# teensyShield1_10.net
KiCad netlist of a schematic drawn in EAGLE
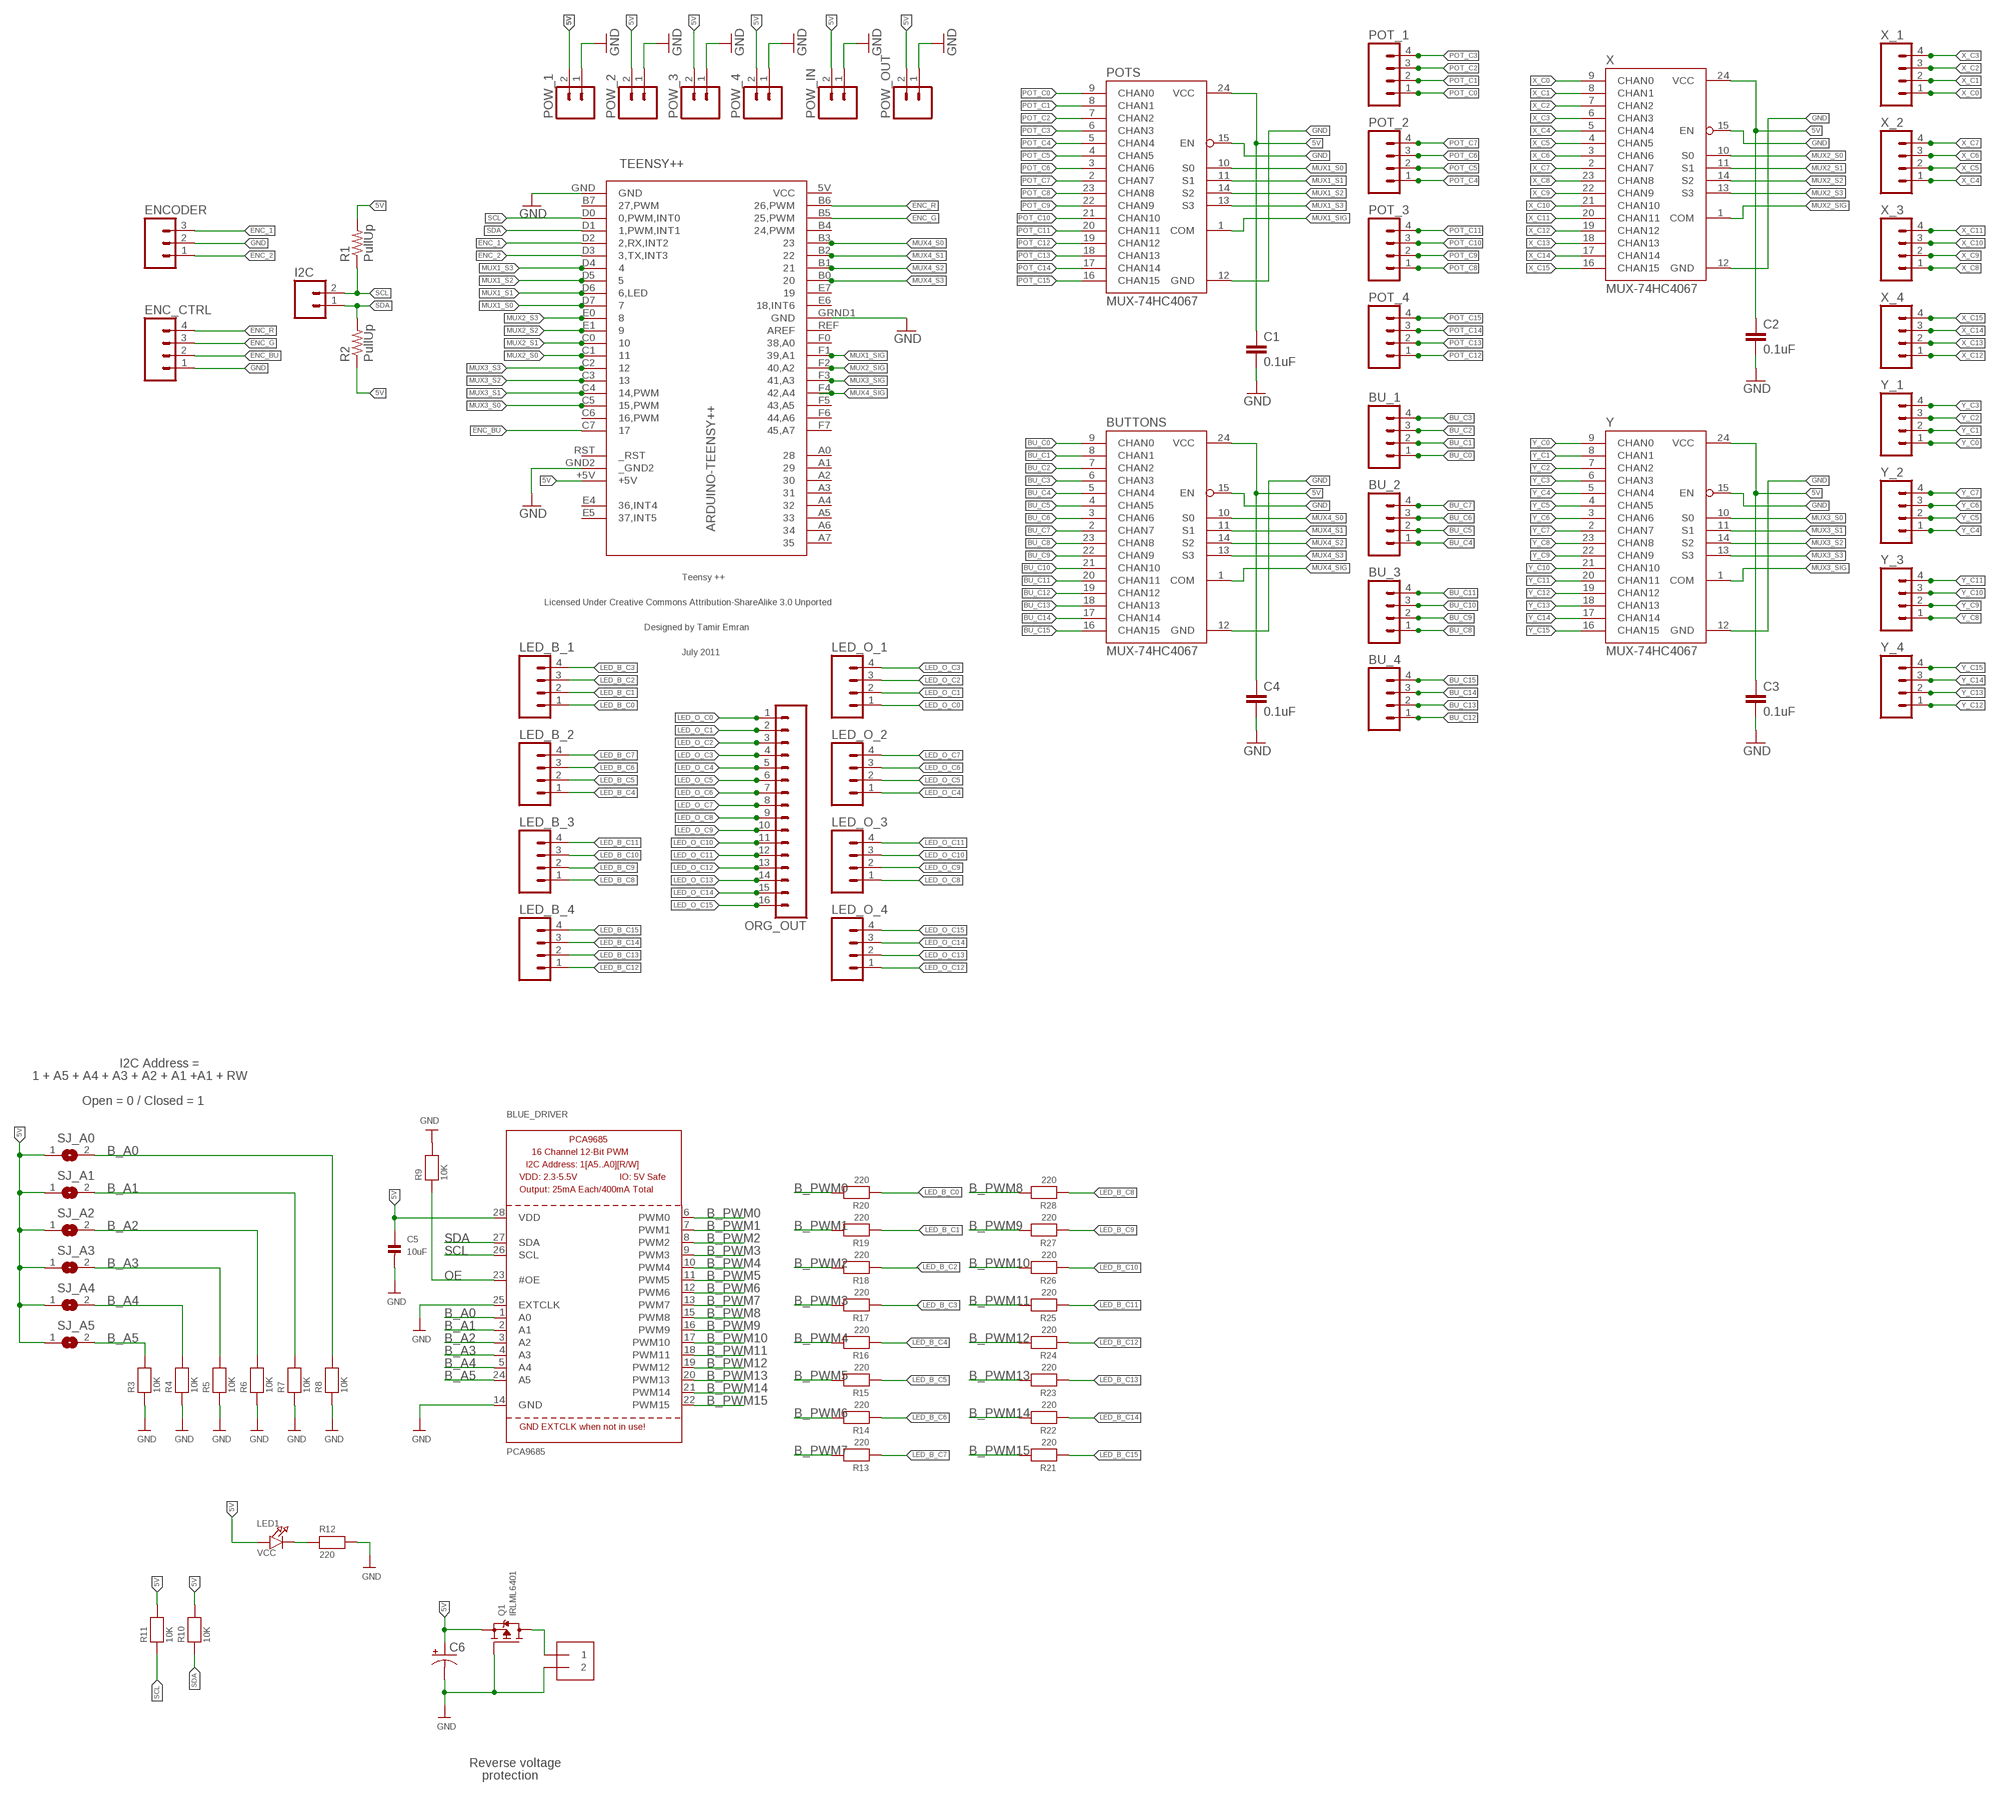
[diagram p0: schematic, sheet 1]

(export (version "E")
  (design (tool "Eeschema 10.0.6"))
  (components
    (comp (ref "BLUE_DRIVER")
      (value "PCA9685")
      (footprint "eagle-import:TSSOP28")
      (libsource (lib "eagle-import") (part "PCA9685"))
    )
    (comp (ref "BUTTONS")
      (value "MUX-74HC4067")
      (footprint "eagle-import:SSOP24")
      (libsource (lib "eagle-import") (part "MUX-74HC4067SMD"))
    )
    (comp (ref "BU_1")
      (value "M04NO_SILK_ALL_ROUND")
      (footprint "eagle-import:1X04_NO_SILK_ALL_ROUND")
      (libsource (lib "eagle-import") (part "M04NO_SILK_ALL_ROUND"))
    )
    (comp (ref "BU_2")
      (value "M04NO_SILK_ALL_ROUND")
      (footprint "eagle-import:1X04_NO_SILK_ALL_ROUND")
      (libsource (lib "eagle-import") (part "M04NO_SILK_ALL_ROUND"))
    )
    (comp (ref "BU_3")
      (value "M04NO_SILK_ALL_ROUND")
      (footprint "eagle-import:1X04_NO_SILK_ALL_ROUND")
      (libsource (lib "eagle-import") (part "M04NO_SILK_ALL_ROUND"))
    )
    (comp (ref "BU_4")
      (value "M04NO_SILK_ALL_ROUND")
      (footprint "eagle-import:1X04_NO_SILK_ALL_ROUND")
      (libsource (lib "eagle-import") (part "M04NO_SILK_ALL_ROUND"))
    )
    (comp (ref "C1")
      (value "0.1uF")
      (footprint "eagle-import:0603")
      (libsource (lib "eagle-import") (part "CAP0603"))
    )
    (comp (ref "C2")
      (value "0.1uF")
      (footprint "eagle-import:0603")
      (libsource (lib "eagle-import") (part "CAP0603"))
    )
    (comp (ref "C3")
      (value "0.1uF")
      (footprint "eagle-import:0603")
      (libsource (lib "eagle-import") (part "CAP0603"))
    )
    (comp (ref "C4")
      (value "0.1uF")
      (footprint "eagle-import:0603")
      (libsource (lib "eagle-import") (part "CAP0603"))
    )
    (comp (ref "C5")
      (value "10uF")
      (footprint "eagle-import:0805")
      (libsource (lib "eagle-import") (part "CAP_CERAMIC0805"))
    )
    (comp (ref "C6")
      (value "CPOL-USE3.5-8")
      (footprint "eagle-import:E3,5-8")
      (libsource (lib "eagle-import") (part "CPOL-USE3.5-8"))
    )
    (comp (ref "ENCODER")
      (value "M031X03_NO_SILK")
      (footprint "eagle-import:1X03_NO_SILK")
      (libsource (lib "eagle-import") (part "M031X03_NO_SILK"))
    )
    (comp (ref "ENC_CTRL")
      (value "M041X04_NO_SILK")
      (footprint "eagle-import:1X04_NO_SILK")
      (libsource (lib "eagle-import") (part "M041X04_NO_SILK"))
    )
    (comp (ref "I2C")
      (value "M02LOCK")
      (footprint "eagle-import:1X02_LOCK")
      (libsource (lib "eagle-import") (part "M02LOCK"))
    )
    (comp (ref "J1")
      (value "TERMBLOCK_1X2-3.5MM")
      (footprint "eagle-import:1X2-3.5MM")
      (libsource (lib "eagle-import") (part "TERMBLOCK_1X2-3.5MM"))
    )
    (comp (ref "LED1")
      (value "VCC")
      (footprint "eagle-import:CHIPLED_0805")
      (libsource (lib "eagle-import") (part "LED0805"))
    )
    (comp (ref "LED_B_1")
      (value "M04NO_SILK_ALL_ROUND")
      (footprint "eagle-import:1X04_NO_SILK_ALL_ROUND")
      (libsource (lib "eagle-import") (part "M04NO_SILK_ALL_ROUND"))
    )
    (comp (ref "LED_B_2")
      (value "M04NO_SILK_ALL_ROUND")
      (footprint "eagle-import:1X04_NO_SILK_ALL_ROUND")
      (libsource (lib "eagle-import") (part "M04NO_SILK_ALL_ROUND"))
    )
    (comp (ref "LED_B_3")
      (value "M04NO_SILK_ALL_ROUND")
      (footprint "eagle-import:1X04_NO_SILK_ALL_ROUND")
      (libsource (lib "eagle-import") (part "M04NO_SILK_ALL_ROUND"))
    )
    (comp (ref "LED_B_4")
      (value "M04NO_SILK_ALL_ROUND")
      (footprint "eagle-import:1X04_NO_SILK_ALL_ROUND")
      (libsource (lib "eagle-import") (part "M04NO_SILK_ALL_ROUND"))
    )
    (comp (ref "LED_O_1")
      (value "M04NO_SILK_ALL_ROUND")
      (footprint "eagle-import:1X04_NO_SILK_ALL_ROUND")
      (libsource (lib "eagle-import") (part "M04NO_SILK_ALL_ROUND"))
    )
    (comp (ref "LED_O_2")
      (value "M04NO_SILK_ALL_ROUND")
      (footprint "eagle-import:1X04_NO_SILK_ALL_ROUND")
      (libsource (lib "eagle-import") (part "M04NO_SILK_ALL_ROUND"))
    )
    (comp (ref "LED_O_3")
      (value "M04NO_SILK_ALL_ROUND")
      (footprint "eagle-import:1X04_NO_SILK_ALL_ROUND")
      (libsource (lib "eagle-import") (part "M04NO_SILK_ALL_ROUND"))
    )
    (comp (ref "LED_O_4")
      (value "M04NO_SILK_ALL_ROUND")
      (footprint "eagle-import:1X04_NO_SILK_ALL_ROUND")
      (libsource (lib "eagle-import") (part "M04NO_SILK_ALL_ROUND"))
    )
    (comp (ref "ORG_OUT")
      (value "M161X16_NO_SILK")
      (footprint "eagle-import:1X16_NO_SILK")
      (libsource (lib "eagle-import") (part "M161X16_NO_SILK"))
    )
    (comp (ref "POTS")
      (value "MUX-74HC4067")
      (footprint "eagle-import:SSOP24")
      (libsource (lib "eagle-import") (part "MUX-74HC4067SMD"))
    )
    (comp (ref "POT_1")
      (value "M04NO_SILK_ALL_ROUND")
      (footprint "eagle-import:1X04_NO_SILK_ALL_ROUND")
      (libsource (lib "eagle-import") (part "M04NO_SILK_ALL_ROUND"))
    )
    (comp (ref "POT_2")
      (value "M04NO_SILK_ALL_ROUND")
      (footprint "eagle-import:1X04_NO_SILK_ALL_ROUND")
      (libsource (lib "eagle-import") (part "M04NO_SILK_ALL_ROUND"))
    )
    (comp (ref "POT_3")
      (value "M04NO_SILK_ALL_ROUND")
      (footprint "eagle-import:1X04_NO_SILK_ALL_ROUND")
      (libsource (lib "eagle-import") (part "M04NO_SILK_ALL_ROUND"))
    )
    (comp (ref "POT_4")
      (value "M04NO_SILK_ALL_ROUND")
      (footprint "eagle-import:1X04_NO_SILK_ALL_ROUND")
      (libsource (lib "eagle-import") (part "M04NO_SILK_ALL_ROUND"))
    )
    (comp (ref "POW_1")
      (value "M02POLAR")
      (footprint "eagle-import:MOLEX-1X2")
      (libsource (lib "eagle-import") (part "M02POLAR"))
    )
    (comp (ref "POW_2")
      (value "M02POLAR")
      (footprint "eagle-import:MOLEX-1X2")
      (libsource (lib "eagle-import") (part "M02POLAR"))
    )
    (comp (ref "POW_3")
      (value "M02POLAR")
      (footprint "eagle-import:MOLEX-1X2")
      (libsource (lib "eagle-import") (part "M02POLAR"))
    )
    (comp (ref "POW_4")
      (value "M02POLAR")
      (footprint "eagle-import:MOLEX-1X2")
      (libsource (lib "eagle-import") (part "M02POLAR"))
    )
    (comp (ref "POW_IN")
      (value "M02POLAR")
      (footprint "eagle-import:MOLEX-1X2")
      (libsource (lib "eagle-import") (part "M02POLAR"))
    )
    (comp (ref "POW_OUT")
      (value "M02POLAR")
      (footprint "eagle-import:MOLEX-1X2")
      (libsource (lib "eagle-import") (part "M02POLAR"))
    )
    (comp (ref "Q1")
      (value "IRLML6401")
      (footprint "eagle-import:SOT23-WIDE")
      (libsource (lib "eagle-import") (part "MOSFET-PWIDE"))
    )
    (comp (ref "R1")
      (value "PullUp")
      (footprint "eagle-import:AXIAL-0.3")
      (libsource (lib "eagle-import") (part "10KOHM-1/4W5%(PTH)"))
    )
    (comp (ref "R2")
      (value "PullUp")
      (footprint "eagle-import:AXIAL-0.3")
      (libsource (lib "eagle-import") (part "10KOHM-1/4W5%(PTH)"))
    )
    (comp (ref "R3")
      (value "10K")
      (footprint "eagle-import:0805")
      (libsource (lib "eagle-import") (part "RESISTOR0805"))
    )
    (comp (ref "R4")
      (value "10K")
      (footprint "eagle-import:0805")
      (libsource (lib "eagle-import") (part "RESISTOR0805"))
    )
    (comp (ref "R5")
      (value "10K")
      (footprint "eagle-import:0805")
      (libsource (lib "eagle-import") (part "RESISTOR0805"))
    )
    (comp (ref "R6")
      (value "10K")
      (footprint "eagle-import:0805")
      (libsource (lib "eagle-import") (part "RESISTOR0805"))
    )
    (comp (ref "R7")
      (value "10K")
      (footprint "eagle-import:0805")
      (libsource (lib "eagle-import") (part "RESISTOR0805"))
    )
    (comp (ref "R8")
      (value "10K")
      (footprint "eagle-import:0805")
      (libsource (lib "eagle-import") (part "RESISTOR0805"))
    )
    (comp (ref "R9")
      (value "10K")
      (footprint "eagle-import:0805")
      (libsource (lib "eagle-import") (part "RESISTOR0805"))
    )
    (comp (ref "R10")
      (value "10K")
      (footprint "eagle-import:0805")
      (libsource (lib "eagle-import") (part "RESISTOR0805"))
    )
    (comp (ref "R11")
      (value "10K")
      (footprint "eagle-import:0805")
      (libsource (lib "eagle-import") (part "RESISTOR0805"))
    )
    (comp (ref "R12")
      (value "220")
      (footprint "eagle-import:0805")
      (libsource (lib "eagle-import") (part "RESISTOR0805"))
    )
    (comp (ref "R13")
      (value "220")
      (footprint "eagle-import:0805")
      (libsource (lib "eagle-import") (part "RESISTOR0805"))
    )
    (comp (ref "R14")
      (value "220")
      (footprint "eagle-import:0805")
      (libsource (lib "eagle-import") (part "RESISTOR0805"))
    )
    (comp (ref "R15")
      (value "220")
      (footprint "eagle-import:0805")
      (libsource (lib "eagle-import") (part "RESISTOR0805"))
    )
    (comp (ref "R16")
      (value "220")
      (footprint "eagle-import:0805")
      (libsource (lib "eagle-import") (part "RESISTOR0805"))
    )
    (comp (ref "R17")
      (value "220")
      (footprint "eagle-import:0805")
      (libsource (lib "eagle-import") (part "RESISTOR0805"))
    )
    (comp (ref "R18")
      (value "220")
      (footprint "eagle-import:0805")
      (libsource (lib "eagle-import") (part "RESISTOR0805"))
    )
    (comp (ref "R19")
      (value "220")
      (footprint "eagle-import:0805")
      (libsource (lib "eagle-import") (part "RESISTOR0805"))
    )
    (comp (ref "R20")
      (value "220")
      (footprint "eagle-import:0805")
      (libsource (lib "eagle-import") (part "RESISTOR0805"))
    )
    (comp (ref "R21")
      (value "220")
      (footprint "eagle-import:0805")
      (libsource (lib "eagle-import") (part "RESISTOR0805"))
    )
    (comp (ref "R22")
      (value "220")
      (footprint "eagle-import:0805")
      (libsource (lib "eagle-import") (part "RESISTOR0805"))
    )
    (comp (ref "R23")
      (value "220")
      (footprint "eagle-import:0805")
      (libsource (lib "eagle-import") (part "RESISTOR0805"))
    )
    (comp (ref "R24")
      (value "220")
      (footprint "eagle-import:0805")
      (libsource (lib "eagle-import") (part "RESISTOR0805"))
    )
    (comp (ref "R25")
      (value "220")
      (footprint "eagle-import:0805")
      (libsource (lib "eagle-import") (part "RESISTOR0805"))
    )
    (comp (ref "R26")
      (value "220")
      (footprint "eagle-import:0805")
      (libsource (lib "eagle-import") (part "RESISTOR0805"))
    )
    (comp (ref "R27")
      (value "220")
      (footprint "eagle-import:0805")
      (libsource (lib "eagle-import") (part "RESISTOR0805"))
    )
    (comp (ref "R28")
      (value "220")
      (footprint "eagle-import:0805")
      (libsource (lib "eagle-import") (part "RESISTOR0805"))
    )
    (comp (ref "SJ_A0")
      (value "SOLDERJUMPERREFLOW_NOPASTE")
      (footprint "eagle-import:SOLDERJUMPER_REFLOW_NOPASTE")
      (libsource (lib "eagle-import") (part "SOLDERJUMPERREFLOW_NOPASTE"))
    )
    (comp (ref "SJ_A1")
      (value "SOLDERJUMPERREFLOW_NOPASTE")
      (footprint "eagle-import:SOLDERJUMPER_REFLOW_NOPASTE")
      (libsource (lib "eagle-import") (part "SOLDERJUMPERREFLOW_NOPASTE"))
    )
    (comp (ref "SJ_A2")
      (value "SOLDERJUMPERREFLOW_NOPASTE")
      (footprint "eagle-import:SOLDERJUMPER_REFLOW_NOPASTE")
      (libsource (lib "eagle-import") (part "SOLDERJUMPERREFLOW_NOPASTE"))
    )
    (comp (ref "SJ_A3")
      (value "SOLDERJUMPERREFLOW_NOPASTE")
      (footprint "eagle-import:SOLDERJUMPER_REFLOW_NOPASTE")
      (libsource (lib "eagle-import") (part "SOLDERJUMPERREFLOW_NOPASTE"))
    )
    (comp (ref "SJ_A4")
      (value "SOLDERJUMPERREFLOW_NOPASTE")
      (footprint "eagle-import:SOLDERJUMPER_REFLOW_NOPASTE")
      (libsource (lib "eagle-import") (part "SOLDERJUMPERREFLOW_NOPASTE"))
    )
    (comp (ref "SJ_A5")
      (value "SOLDERJUMPERREFLOW_NOPASTE")
      (footprint "eagle-import:SOLDERJUMPER_REFLOW_NOPASTE")
      (libsource (lib "eagle-import") (part "SOLDERJUMPERREFLOW_NOPASTE"))
    )
    (comp (ref "TEENSY++")
      (value "ARDUINO-TEENSY++")
      (footprint "eagle-import:TEENSY++")
      (libsource (lib "eagle-import") (part "ARDUINO-TEENSY++"))
    )
    (comp (ref "X")
      (value "MUX-74HC4067")
      (footprint "eagle-import:SSOP24")
      (libsource (lib "eagle-import") (part "MUX-74HC4067SMD"))
    )
    (comp (ref "X_1")
      (value "M04NO_SILK_ALL_ROUND")
      (footprint "eagle-import:1X04_NO_SILK_ALL_ROUND")
      (libsource (lib "eagle-import") (part "M04NO_SILK_ALL_ROUND"))
    )
    (comp (ref "X_2")
      (value "M04NO_SILK_ALL_ROUND")
      (footprint "eagle-import:1X04_NO_SILK_ALL_ROUND")
      (libsource (lib "eagle-import") (part "M04NO_SILK_ALL_ROUND"))
    )
    (comp (ref "X_3")
      (value "M04NO_SILK_ALL_ROUND")
      (footprint "eagle-import:1X04_NO_SILK_ALL_ROUND")
      (libsource (lib "eagle-import") (part "M04NO_SILK_ALL_ROUND"))
    )
    (comp (ref "X_4")
      (value "M04NO_SILK_ALL_ROUND")
      (footprint "eagle-import:1X04_NO_SILK_ALL_ROUND")
      (libsource (lib "eagle-import") (part "M04NO_SILK_ALL_ROUND"))
    )
    (comp (ref "Y")
      (value "MUX-74HC4067")
      (footprint "eagle-import:SSOP24")
      (libsource (lib "eagle-import") (part "MUX-74HC4067SMD"))
    )
    (comp (ref "Y_1")
      (value "M04NO_SILK_ALL_ROUND")
      (footprint "eagle-import:1X04_NO_SILK_ALL_ROUND")
      (libsource (lib "eagle-import") (part "M04NO_SILK_ALL_ROUND"))
    )
    (comp (ref "Y_2")
      (value "M04NO_SILK_ALL_ROUND")
      (footprint "eagle-import:1X04_NO_SILK_ALL_ROUND")
      (libsource (lib "eagle-import") (part "M04NO_SILK_ALL_ROUND"))
    )
    (comp (ref "Y_3")
      (value "M04NO_SILK_ALL_ROUND")
      (footprint "eagle-import:1X04_NO_SILK_ALL_ROUND")
      (libsource (lib "eagle-import") (part "M04NO_SILK_ALL_ROUND"))
    )
    (comp (ref "Y_4")
      (value "M04NO_SILK_ALL_ROUND")
      (footprint "eagle-import:1X04_NO_SILK_ALL_ROUND")
      (libsource (lib "eagle-import") (part "M04NO_SILK_ALL_ROUND"))
    )
  )
  (nets
    (net (code "1") (name "/B_A0") (class "Default")
      (node (ref "BLUE_DRIVER") (pin "1") (pinfunction "A0_1") (pintype "bidirectional"))
      (node (ref "R8") (pin "2") (pinfunction "2_2") (pintype "passive"))
      (node (ref "SJ_A0") (pin "2") (pinfunction "2_2") (pintype "passive"))
    )
    (net (code "2") (name "/B_A1") (class "Default")
      (node (ref "BLUE_DRIVER") (pin "2") (pinfunction "A1_2") (pintype "bidirectional"))
      (node (ref "R7") (pin "2") (pinfunction "2_2") (pintype "passive"))
      (node (ref "SJ_A1") (pin "2") (pinfunction "2_2") (pintype "passive"))
    )
    (net (code "3") (name "/B_A2") (class "Default")
      (node (ref "BLUE_DRIVER") (pin "3") (pinfunction "A2_3") (pintype "bidirectional"))
      (node (ref "R6") (pin "2") (pinfunction "2_2") (pintype "passive"))
      (node (ref "SJ_A2") (pin "2") (pinfunction "2_2") (pintype "passive"))
    )
    (net (code "4") (name "/B_A3") (class "Default")
      (node (ref "BLUE_DRIVER") (pin "4") (pinfunction "A3_4") (pintype "bidirectional"))
      (node (ref "R5") (pin "2") (pinfunction "2_2") (pintype "passive"))
      (node (ref "SJ_A3") (pin "2") (pinfunction "2_2") (pintype "passive"))
    )
    (net (code "5") (name "/B_A4") (class "Default")
      (node (ref "BLUE_DRIVER") (pin "5") (pinfunction "A4_5") (pintype "bidirectional"))
      (node (ref "R4") (pin "2") (pinfunction "2_2") (pintype "passive"))
      (node (ref "SJ_A4") (pin "2") (pinfunction "2_2") (pintype "passive"))
    )
    (net (code "6") (name "/B_A5") (class "Default")
      (node (ref "BLUE_DRIVER") (pin "24") (pinfunction "A5_24") (pintype "bidirectional"))
      (node (ref "R3") (pin "2") (pinfunction "2_2") (pintype "passive"))
      (node (ref "SJ_A5") (pin "2") (pinfunction "2_2") (pintype "passive"))
    )
    (net (code "7") (name "/B_PWM0") (class "Default")
      (node (ref "BLUE_DRIVER") (pin "6") (pinfunction "PWM0_6") (pintype "output"))
      (node (ref "R20") (pin "2") (pinfunction "2_2") (pintype "passive"))
    )
    (net (code "8") (name "/B_PWM1") (class "Default")
      (node (ref "BLUE_DRIVER") (pin "7") (pinfunction "PWM1_7") (pintype "output"))
      (node (ref "R19") (pin "2") (pinfunction "2_2") (pintype "passive"))
    )
    (net (code "9") (name "/B_PWM2") (class "Default")
      (node (ref "BLUE_DRIVER") (pin "8") (pinfunction "PWM2_8") (pintype "output"))
      (node (ref "R18") (pin "2") (pinfunction "2_2") (pintype "passive"))
    )
    (net (code "10") (name "/B_PWM3") (class "Default")
      (node (ref "BLUE_DRIVER") (pin "9") (pinfunction "PWM3_9") (pintype "output"))
      (node (ref "R17") (pin "2") (pinfunction "2_2") (pintype "passive"))
    )
    (net (code "11") (name "/B_PWM4") (class "Default")
      (node (ref "BLUE_DRIVER") (pin "10") (pinfunction "PWM4_10") (pintype "output"))
      (node (ref "R16") (pin "2") (pinfunction "2_2") (pintype "passive"))
    )
    (net (code "12") (name "/B_PWM5") (class "Default")
      (node (ref "BLUE_DRIVER") (pin "11") (pinfunction "PWM5_11") (pintype "output"))
      (node (ref "R15") (pin "2") (pinfunction "2_2") (pintype "passive"))
    )
    (net (code "13") (name "/B_PWM6") (class "Default")
      (node (ref "BLUE_DRIVER") (pin "12") (pinfunction "PWM6_12") (pintype "output"))
      (node (ref "R14") (pin "2") (pinfunction "2_2") (pintype "passive"))
    )
    (net (code "14") (name "/B_PWM7") (class "Default")
      (node (ref "BLUE_DRIVER") (pin "13") (pinfunction "PWM7_13") (pintype "output"))
      (node (ref "R13") (pin "2") (pinfunction "2_2") (pintype "passive"))
    )
    (net (code "15") (name "/B_PWM8") (class "Default")
      (node (ref "BLUE_DRIVER") (pin "15") (pinfunction "PWM8_15") (pintype "output"))
      (node (ref "R28") (pin "2") (pinfunction "2_2") (pintype "passive"))
    )
    (net (code "16") (name "/B_PWM9") (class "Default")
      (node (ref "BLUE_DRIVER") (pin "16") (pinfunction "PWM9_16") (pintype "output"))
      (node (ref "R27") (pin "2") (pinfunction "2_2") (pintype "passive"))
    )
    (net (code "17") (name "/B_PWM10") (class "Default")
      (node (ref "BLUE_DRIVER") (pin "17") (pinfunction "PWM10_17") (pintype "output"))
      (node (ref "R26") (pin "2") (pinfunction "2_2") (pintype "passive"))
    )
    (net (code "18") (name "/B_PWM11") (class "Default")
      (node (ref "BLUE_DRIVER") (pin "18") (pinfunction "PWM11_18") (pintype "output"))
      (node (ref "R25") (pin "2") (pinfunction "2_2") (pintype "passive"))
    )
    (net (code "19") (name "/B_PWM12") (class "Default")
      (node (ref "BLUE_DRIVER") (pin "19") (pinfunction "PWM12_19") (pintype "output"))
      (node (ref "R24") (pin "2") (pinfunction "2_2") (pintype "passive"))
    )
    (net (code "20") (name "/B_PWM13") (class "Default")
      (node (ref "BLUE_DRIVER") (pin "20") (pinfunction "PWM13_20") (pintype "output"))
      (node (ref "R23") (pin "2") (pinfunction "2_2") (pintype "passive"))
    )
    (net (code "21") (name "/B_PWM14") (class "Default")
      (node (ref "BLUE_DRIVER") (pin "21") (pinfunction "PWM14_21") (pintype "output"))
      (node (ref "R22") (pin "2") (pinfunction "2_2") (pintype "passive"))
    )
    (net (code "22") (name "/B_PWM15") (class "Default")
      (node (ref "BLUE_DRIVER") (pin "22") (pinfunction "PWM15_22") (pintype "output"))
      (node (ref "R21") (pin "2") (pinfunction "2_2") (pintype "passive"))
    )
    (net (code "23") (name "/OE") (class "Default")
      (node (ref "BLUE_DRIVER") (pin "23") (pinfunction "#OE_23") (pintype "input"))
      (node (ref "R9") (pin "1") (pinfunction "1_1") (pintype "passive"))
    )
    (net (code "24") (name "/VCC") (class "Default")
      (node (ref "TEENSY++") (pin "5V") (pinfunction "VCC_5V") (pintype "power_in"))
    )
    (net (code "25") (name "5V") (class "Default")
      (node (ref "BLUE_DRIVER") (pin "28") (pinfunction "VDD_28") (pintype "power_in"))
      (node (ref "BUTTONS") (pin "24") (pinfunction "VCC_24") (pintype "bidirectional"))
      (node (ref "C1") (pin "1") (pinfunction "1_1") (pintype "passive"))
      (node (ref "C2") (pin "1") (pinfunction "1_1") (pintype "passive"))
      (node (ref "C3") (pin "1") (pinfunction "1_1") (pintype "passive"))
      (node (ref "C4") (pin "1") (pinfunction "1_1") (pintype "passive"))
      (node (ref "C5") (pin "1") (pinfunction "P$1_1") (pintype "passive"))
      (node (ref "C6") (pin "+") (pinfunction "+_+") (pintype "passive"))
      (node (ref "LED1") (pin "A") (pinfunction "A_A") (pintype "passive"))
      (node (ref "POTS") (pin "24") (pinfunction "VCC_24") (pintype "bidirectional"))
      (node (ref "POW_1") (pin "2") (pinfunction "2_2") (pintype "passive"))
      (node (ref "POW_2") (pin "2") (pinfunction "2_2") (pintype "passive"))
      (node (ref "POW_3") (pin "2") (pinfunction "2_2") (pintype "passive"))
      (node (ref "POW_4") (pin "2") (pinfunction "2_2") (pintype "passive"))
      (node (ref "POW_IN") (pin "2") (pinfunction "2_2") (pintype "passive"))
      (node (ref "POW_OUT") (pin "2") (pinfunction "2_2") (pintype "passive"))
      (node (ref "Q1") (pin "2") (pinfunction "S_2") (pintype "passive"))
      (node (ref "R1") (pin "P$2") (pinfunction "2_P$2") (pintype "passive"))
      (node (ref "R10") (pin "2") (pinfunction "2_2") (pintype "passive"))
      (node (ref "R11") (pin "2") (pinfunction "2_2") (pintype "passive"))
      (node (ref "R2") (pin "P$1") (pinfunction "1_P$1") (pintype "passive"))
      (node (ref "SJ_A0") (pin "1") (pinfunction "1_1") (pintype "passive"))
      (node (ref "SJ_A1") (pin "1") (pinfunction "1_1") (pintype "passive"))
      (node (ref "SJ_A2") (pin "1") (pinfunction "1_1") (pintype "passive"))
      (node (ref "SJ_A3") (pin "1") (pinfunction "1_1") (pintype "passive"))
      (node (ref "SJ_A4") (pin "1") (pinfunction "1_1") (pintype "passive"))
      (node (ref "SJ_A5") (pin "1") (pinfunction "1_1") (pintype "passive"))
      (node (ref "TEENSY++") (pin "+5V") (pinfunction "+5V_+5V") (pintype "power_in"))
      (node (ref "X") (pin "24") (pinfunction "VCC_24") (pintype "bidirectional"))
      (node (ref "Y") (pin "24") (pinfunction "VCC_24") (pintype "bidirectional"))
    )
    (net (code "26") (name "BU_C0") (class "Default")
      (node (ref "BUTTONS") (pin "9") (pinfunction "CHAN0_9") (pintype "bidirectional"))
      (node (ref "BU_1") (pin "1") (pinfunction "1_1") (pintype "passive"))
    )
    (net (code "27") (name "BU_C1") (class "Default")
      (node (ref "BUTTONS") (pin "8") (pinfunction "CHAN1_8") (pintype "bidirectional"))
      (node (ref "BU_1") (pin "2") (pinfunction "2_2") (pintype "passive"))
    )
    (net (code "28") (name "BU_C2") (class "Default")
      (node (ref "BUTTONS") (pin "7") (pinfunction "CHAN2_7") (pintype "bidirectional"))
      (node (ref "BU_1") (pin "3") (pinfunction "3_3") (pintype "passive"))
    )
    (net (code "29") (name "BU_C3") (class "Default")
      (node (ref "BUTTONS") (pin "6") (pinfunction "CHAN3_6") (pintype "bidirectional"))
      (node (ref "BU_1") (pin "4") (pinfunction "4_4") (pintype "passive"))
    )
    (net (code "30") (name "BU_C4") (class "Default")
      (node (ref "BUTTONS") (pin "5") (pinfunction "CHAN4_5") (pintype "bidirectional"))
      (node (ref "BU_2") (pin "1") (pinfunction "1_1") (pintype "passive"))
    )
    (net (code "31") (name "BU_C5") (class "Default")
      (node (ref "BUTTONS") (pin "4") (pinfunction "CHAN5_4") (pintype "bidirectional"))
      (node (ref "BU_2") (pin "2") (pinfunction "2_2") (pintype "passive"))
    )
    (net (code "32") (name "BU_C6") (class "Default")
      (node (ref "BUTTONS") (pin "3") (pinfunction "CHAN6_3") (pintype "bidirectional"))
      (node (ref "BU_2") (pin "3") (pinfunction "3_3") (pintype "passive"))
    )
    (net (code "33") (name "BU_C7") (class "Default")
      (node (ref "BUTTONS") (pin "2") (pinfunction "CHAN7_2") (pintype "bidirectional"))
      (node (ref "BU_2") (pin "4") (pinfunction "4_4") (pintype "passive"))
    )
    (net (code "34") (name "BU_C8") (class "Default")
      (node (ref "BUTTONS") (pin "23") (pinfunction "CHAN8_23") (pintype "bidirectional"))
      (node (ref "BU_3") (pin "1") (pinfunction "1_1") (pintype "passive"))
    )
    (net (code "35") (name "BU_C9") (class "Default")
      (node (ref "BUTTONS") (pin "22") (pinfunction "CHAN9_22") (pintype "bidirectional"))
      (node (ref "BU_3") (pin "2") (pinfunction "2_2") (pintype "passive"))
    )
    (net (code "36") (name "BU_C10") (class "Default")
      (node (ref "BUTTONS") (pin "21") (pinfunction "CHAN10_21") (pintype "bidirectional"))
      (node (ref "BU_3") (pin "3") (pinfunction "3_3") (pintype "passive"))
    )
    (net (code "37") (name "BU_C11") (class "Default")
      (node (ref "BUTTONS") (pin "20") (pinfunction "CHAN11_20") (pintype "bidirectional"))
      (node (ref "BU_3") (pin "4") (pinfunction "4_4") (pintype "passive"))
    )
    (net (code "38") (name "BU_C12") (class "Default")
      (node (ref "BUTTONS") (pin "19") (pinfunction "CHAN12_19") (pintype "bidirectional"))
      (node (ref "BU_4") (pin "1") (pinfunction "1_1") (pintype "passive"))
    )
    (net (code "39") (name "BU_C13") (class "Default")
      (node (ref "BUTTONS") (pin "18") (pinfunction "CHAN13_18") (pintype "bidirectional"))
      (node (ref "BU_4") (pin "2") (pinfunction "2_2") (pintype "passive"))
    )
    (net (code "40") (name "BU_C14") (class "Default")
      (node (ref "BUTTONS") (pin "17") (pinfunction "CHAN14_17") (pintype "bidirectional"))
      (node (ref "BU_4") (pin "3") (pinfunction "3_3") (pintype "passive"))
    )
    (net (code "41") (name "BU_C15") (class "Default")
      (node (ref "BUTTONS") (pin "16") (pinfunction "CHAN15_16") (pintype "bidirectional"))
      (node (ref "BU_4") (pin "4") (pinfunction "4_4") (pintype "passive"))
    )
    (net (code "42") (name "ENC_1") (class "Default")
      (node (ref "ENCODER") (pin "3") (pinfunction "3_3") (pintype "passive"))
      (node (ref "TEENSY++") (pin "D2") (pinfunction "2,RX,INT2_D2") (pintype "bidirectional"))
    )
    (net (code "43") (name "ENC_2") (class "Default")
      (node (ref "ENCODER") (pin "1") (pinfunction "1_1") (pintype "passive"))
      (node (ref "TEENSY++") (pin "D3") (pinfunction "3,TX,INT3_D3") (pintype "bidirectional"))
    )
    (net (code "44") (name "ENC_BU") (class "Default")
      (node (ref "ENC_CTRL") (pin "2") (pinfunction "2_2") (pintype "passive"))
      (node (ref "TEENSY++") (pin "C7") (pinfunction "17_C7") (pintype "bidirectional"))
    )
    (net (code "45") (name "ENC_G") (class "Default")
      (node (ref "ENC_CTRL") (pin "3") (pinfunction "3_3") (pintype "passive"))
      (node (ref "TEENSY++") (pin "B5") (pinfunction "25,PWM_B5") (pintype "bidirectional"))
    )
    (net (code "46") (name "ENC_R") (class "Default")
      (node (ref "ENC_CTRL") (pin "4") (pinfunction "4_4") (pintype "passive"))
      (node (ref "TEENSY++") (pin "B6") (pinfunction "26,PWM_B6") (pintype "bidirectional"))
    )
    (net (code "47") (name "GND") (class "Default")
      (node (ref "BLUE_DRIVER") (pin "14") (pinfunction "GND_14") (pintype "power_in"))
      (node (ref "BLUE_DRIVER") (pin "25") (pinfunction "EXTCLK_25") (pintype "input"))
      (node (ref "BUTTONS") (pin "12") (pinfunction "GND_12") (pintype "bidirectional"))
      (node (ref "BUTTONS") (pin "15") (pinfunction "EN_15") (pintype "input"))
      (node (ref "C1") (pin "2") (pinfunction "2_2") (pintype "passive"))
      (node (ref "C2") (pin "2") (pinfunction "2_2") (pintype "passive"))
      (node (ref "C3") (pin "2") (pinfunction "2_2") (pintype "passive"))
      (node (ref "C4") (pin "2") (pinfunction "2_2") (pintype "passive"))
      (node (ref "C5") (pin "2") (pinfunction "P$2_2") (pintype "passive"))
      (node (ref "C6") (pin "-") (pinfunction "-_-") (pintype "passive"))
      (node (ref "ENCODER") (pin "2") (pinfunction "2_2") (pintype "passive"))
      (node (ref "ENC_CTRL") (pin "1") (pinfunction "1_1") (pintype "passive"))
      (node (ref "J1") (pin "2") (pinfunction "2_2") (pintype "passive"))
      (node (ref "POTS") (pin "12") (pinfunction "GND_12") (pintype "bidirectional"))
      (node (ref "POTS") (pin "15") (pinfunction "EN_15") (pintype "input"))
      (node (ref "POW_1") (pin "1") (pinfunction "1_1") (pintype "passive"))
      (node (ref "POW_2") (pin "1") (pinfunction "1_1") (pintype "passive"))
      (node (ref "POW_3") (pin "1") (pinfunction "1_1") (pintype "passive"))
      (node (ref "POW_4") (pin "1") (pinfunction "1_1") (pintype "passive"))
      (node (ref "POW_IN") (pin "1") (pinfunction "1_1") (pintype "passive"))
      (node (ref "POW_OUT") (pin "1") (pinfunction "1_1") (pintype "passive"))
      (node (ref "Q1") (pin "1") (pinfunction "G_1") (pintype "passive"))
      (node (ref "R12") (pin "2") (pinfunction "2_2") (pintype "passive"))
      (node (ref "R3") (pin "1") (pinfunction "1_1") (pintype "passive"))
      (node (ref "R4") (pin "1") (pinfunction "1_1") (pintype "passive"))
      (node (ref "R5") (pin "1") (pinfunction "1_1") (pintype "passive"))
      (node (ref "R6") (pin "1") (pinfunction "1_1") (pintype "passive"))
      (node (ref "R7") (pin "1") (pinfunction "1_1") (pintype "passive"))
      (node (ref "R8") (pin "1") (pinfunction "1_1") (pintype "passive"))
      (node (ref "R9") (pin "2") (pinfunction "2_2") (pintype "passive"))
      (node (ref "TEENSY++") (pin "GND") (pinfunction "GND_GND") (pintype "power_in"))
      (node (ref "TEENSY++") (pin "GND2") (pinfunction "_GND2_GND2") (pintype "power_in"))
      (node (ref "TEENSY++") (pin "GRND1") (pinfunction "GND_GRND1") (pintype "power_in"))
      (node (ref "X") (pin "12") (pinfunction "GND_12") (pintype "bidirectional"))
      (node (ref "X") (pin "15") (pinfunction "EN_15") (pintype "input"))
      (node (ref "Y") (pin "12") (pinfunction "GND_12") (pintype "bidirectional"))
      (node (ref "Y") (pin "15") (pinfunction "EN_15") (pintype "input"))
    )
    (net (code "48") (name "LED_B_C0") (class "Default")
      (node (ref "LED_B_1") (pin "1") (pinfunction "1_1") (pintype "passive"))
      (node (ref "R20") (pin "1") (pinfunction "1_1") (pintype "passive"))
    )
    (net (code "49") (name "LED_B_C1") (class "Default")
      (node (ref "LED_B_1") (pin "2") (pinfunction "2_2") (pintype "passive"))
      (node (ref "R19") (pin "1") (pinfunction "1_1") (pintype "passive"))
    )
    (net (code "50") (name "LED_B_C2") (class "Default")
      (node (ref "LED_B_1") (pin "3") (pinfunction "3_3") (pintype "passive"))
      (node (ref "R18") (pin "1") (pinfunction "1_1") (pintype "passive"))
    )
    (net (code "51") (name "LED_B_C3") (class "Default")
      (node (ref "LED_B_1") (pin "4") (pinfunction "4_4") (pintype "passive"))
      (node (ref "R17") (pin "1") (pinfunction "1_1") (pintype "passive"))
    )
    (net (code "52") (name "LED_B_C4") (class "Default")
      (node (ref "LED_B_2") (pin "1") (pinfunction "1_1") (pintype "passive"))
      (node (ref "R16") (pin "1") (pinfunction "1_1") (pintype "passive"))
    )
    (net (code "53") (name "LED_B_C5") (class "Default")
      (node (ref "LED_B_2") (pin "2") (pinfunction "2_2") (pintype "passive"))
      (node (ref "R15") (pin "1") (pinfunction "1_1") (pintype "passive"))
    )
    (net (code "54") (name "LED_B_C6") (class "Default")
      (node (ref "LED_B_2") (pin "3") (pinfunction "3_3") (pintype "passive"))
      (node (ref "R14") (pin "1") (pinfunction "1_1") (pintype "passive"))
    )
    (net (code "55") (name "LED_B_C7") (class "Default")
      (node (ref "LED_B_2") (pin "4") (pinfunction "4_4") (pintype "passive"))
      (node (ref "R13") (pin "1") (pinfunction "1_1") (pintype "passive"))
    )
    (net (code "56") (name "LED_B_C8") (class "Default")
      (node (ref "LED_B_3") (pin "1") (pinfunction "1_1") (pintype "passive"))
      (node (ref "R28") (pin "1") (pinfunction "1_1") (pintype "passive"))
    )
    (net (code "57") (name "LED_B_C9") (class "Default")
      (node (ref "LED_B_3") (pin "2") (pinfunction "2_2") (pintype "passive"))
      (node (ref "R27") (pin "1") (pinfunction "1_1") (pintype "passive"))
    )
    (net (code "58") (name "LED_B_C10") (class "Default")
      (node (ref "LED_B_3") (pin "3") (pinfunction "3_3") (pintype "passive"))
      (node (ref "R26") (pin "1") (pinfunction "1_1") (pintype "passive"))
    )
    (net (code "59") (name "LED_B_C11") (class "Default")
      (node (ref "LED_B_3") (pin "4") (pinfunction "4_4") (pintype "passive"))
      (node (ref "R25") (pin "1") (pinfunction "1_1") (pintype "passive"))
    )
    (net (code "60") (name "LED_B_C12") (class "Default")
      (node (ref "LED_B_4") (pin "1") (pinfunction "1_1") (pintype "passive"))
      (node (ref "R24") (pin "1") (pinfunction "1_1") (pintype "passive"))
    )
    (net (code "61") (name "LED_B_C13") (class "Default")
      (node (ref "LED_B_4") (pin "2") (pinfunction "2_2") (pintype "passive"))
      (node (ref "R23") (pin "1") (pinfunction "1_1") (pintype "passive"))
    )
    (net (code "62") (name "LED_B_C14") (class "Default")
      (node (ref "LED_B_4") (pin "3") (pinfunction "3_3") (pintype "passive"))
      (node (ref "R22") (pin "1") (pinfunction "1_1") (pintype "passive"))
    )
    (net (code "63") (name "LED_B_C15") (class "Default")
      (node (ref "LED_B_4") (pin "4") (pinfunction "4_4") (pintype "passive"))
      (node (ref "R21") (pin "1") (pinfunction "1_1") (pintype "passive"))
    )
    (net (code "64") (name "LED_O_C0") (class "Default")
      (node (ref "LED_O_1") (pin "1") (pinfunction "1_1") (pintype "passive"))
      (node (ref "ORG_OUT") (pin "1") (pinfunction "1_1") (pintype "passive"))
    )
    (net (code "65") (name "LED_O_C1") (class "Default")
      (node (ref "LED_O_1") (pin "2") (pinfunction "2_2") (pintype "passive"))
      (node (ref "ORG_OUT") (pin "2") (pinfunction "2_2") (pintype "passive"))
    )
    (net (code "66") (name "LED_O_C2") (class "Default")
      (node (ref "LED_O_1") (pin "3") (pinfunction "3_3") (pintype "passive"))
      (node (ref "ORG_OUT") (pin "3") (pinfunction "3_3") (pintype "passive"))
    )
    (net (code "67") (name "LED_O_C3") (class "Default")
      (node (ref "LED_O_1") (pin "4") (pinfunction "4_4") (pintype "passive"))
      (node (ref "ORG_OUT") (pin "4") (pinfunction "4_4") (pintype "passive"))
    )
    (net (code "68") (name "LED_O_C4") (class "Default")
      (node (ref "LED_O_2") (pin "1") (pinfunction "1_1") (pintype "passive"))
      (node (ref "ORG_OUT") (pin "5") (pinfunction "5_5") (pintype "passive"))
    )
    (net (code "69") (name "LED_O_C5") (class "Default")
      (node (ref "LED_O_2") (pin "2") (pinfunction "2_2") (pintype "passive"))
      (node (ref "ORG_OUT") (pin "6") (pinfunction "6_6") (pintype "passive"))
    )
    (net (code "70") (name "LED_O_C6") (class "Default")
      (node (ref "LED_O_2") (pin "3") (pinfunction "3_3") (pintype "passive"))
      (node (ref "ORG_OUT") (pin "7") (pinfunction "7_7") (pintype "passive"))
    )
    (net (code "71") (name "LED_O_C7") (class "Default")
      (node (ref "LED_O_2") (pin "4") (pinfunction "4_4") (pintype "passive"))
      (node (ref "ORG_OUT") (pin "8") (pinfunction "8_8") (pintype "passive"))
    )
    (net (code "72") (name "LED_O_C8") (class "Default")
      (node (ref "LED_O_3") (pin "1") (pinfunction "1_1") (pintype "passive"))
      (node (ref "ORG_OUT") (pin "9") (pinfunction "9_9") (pintype "passive"))
    )
    (net (code "73") (name "LED_O_C9") (class "Default")
      (node (ref "LED_O_3") (pin "2") (pinfunction "2_2") (pintype "passive"))
      (node (ref "ORG_OUT") (pin "10") (pinfunction "10_10") (pintype "passive"))
    )
    (net (code "74") (name "LED_O_C10") (class "Default")
      (node (ref "LED_O_3") (pin "3") (pinfunction "3_3") (pintype "passive"))
      (node (ref "ORG_OUT") (pin "11") (pinfunction "11_11") (pintype "passive"))
    )
    (net (code "75") (name "LED_O_C11") (class "Default")
      (node (ref "LED_O_3") (pin "4") (pinfunction "4_4") (pintype "passive"))
      (node (ref "ORG_OUT") (pin "12") (pinfunction "12_12") (pintype "passive"))
    )
    (net (code "76") (name "LED_O_C12") (class "Default")
      (node (ref "LED_O_4") (pin "1") (pinfunction "1_1") (pintype "passive"))
      (node (ref "ORG_OUT") (pin "13") (pinfunction "13_13") (pintype "passive"))
    )
    (net (code "77") (name "LED_O_C13") (class "Default")
      (node (ref "LED_O_4") (pin "2") (pinfunction "2_2") (pintype "passive"))
      (node (ref "ORG_OUT") (pin "14") (pinfunction "14_14") (pintype "passive"))
    )
    (net (code "78") (name "LED_O_C14") (class "Default")
      (node (ref "LED_O_4") (pin "3") (pinfunction "3_3") (pintype "passive"))
      (node (ref "ORG_OUT") (pin "15") (pinfunction "15_15") (pintype "passive"))
    )
    (net (code "79") (name "LED_O_C15") (class "Default")
      (node (ref "LED_O_4") (pin "4") (pinfunction "4_4") (pintype "passive"))
      (node (ref "ORG_OUT") (pin "16") (pinfunction "16_16") (pintype "passive"))
    )
    (net (code "80") (name "MUX1_S0") (class "Default")
      (node (ref "POTS") (pin "10") (pinfunction "S0_10") (pintype "input"))
      (node (ref "TEENSY++") (pin "D7") (pinfunction "7_D7") (pintype "bidirectional"))
    )
    (net (code "81") (name "MUX1_S1") (class "Default")
      (node (ref "POTS") (pin "11") (pinfunction "S1_11") (pintype "input"))
      (node (ref "TEENSY++") (pin "D6") (pinfunction "6,LED_D6") (pintype "bidirectional"))
    )
    (net (code "82") (name "MUX1_S2") (class "Default")
      (node (ref "POTS") (pin "14") (pinfunction "S2_14") (pintype "input"))
      (node (ref "TEENSY++") (pin "D5") (pinfunction "5_D5") (pintype "bidirectional"))
    )
    (net (code "83") (name "MUX1_S3") (class "Default")
      (node (ref "POTS") (pin "13") (pinfunction "S3_13") (pintype "input"))
      (node (ref "TEENSY++") (pin "D4") (pinfunction "4_D4") (pintype "bidirectional"))
    )
    (net (code "84") (name "MUX1_SIG") (class "Default")
      (node (ref "POTS") (pin "1") (pinfunction "COM_1") (pintype "bidirectional"))
      (node (ref "TEENSY++") (pin "F1") (pinfunction "39,A1_F1") (pintype "bidirectional"))
    )
    (net (code "85") (name "MUX2_S0") (class "Default")
      (node (ref "TEENSY++") (pin "C1") (pinfunction "11_C1") (pintype "bidirectional"))
      (node (ref "X") (pin "10") (pinfunction "S0_10") (pintype "input"))
    )
    (net (code "86") (name "MUX2_S1") (class "Default")
      (node (ref "TEENSY++") (pin "C0") (pinfunction "10_C0") (pintype "bidirectional"))
      (node (ref "X") (pin "11") (pinfunction "S1_11") (pintype "input"))
    )
    (net (code "87") (name "MUX2_S2") (class "Default")
      (node (ref "TEENSY++") (pin "E1") (pinfunction "9_E1") (pintype "bidirectional"))
      (node (ref "X") (pin "14") (pinfunction "S2_14") (pintype "input"))
    )
    (net (code "88") (name "MUX2_S3") (class "Default")
      (node (ref "TEENSY++") (pin "E0") (pinfunction "8_E0") (pintype "bidirectional"))
      (node (ref "X") (pin "13") (pinfunction "S3_13") (pintype "input"))
    )
    (net (code "89") (name "MUX2_SIG") (class "Default")
      (node (ref "TEENSY++") (pin "F2") (pinfunction "40,A2_F2") (pintype "bidirectional"))
      (node (ref "X") (pin "1") (pinfunction "COM_1") (pintype "bidirectional"))
    )
    (net (code "90") (name "MUX3_S0") (class "Default")
      (node (ref "TEENSY++") (pin "C5") (pinfunction "15,PWM_C5") (pintype "bidirectional"))
      (node (ref "Y") (pin "10") (pinfunction "S0_10") (pintype "input"))
    )
    (net (code "91") (name "MUX3_S1") (class "Default")
      (node (ref "TEENSY++") (pin "C4") (pinfunction "14,PWM_C4") (pintype "bidirectional"))
      (node (ref "Y") (pin "11") (pinfunction "S1_11") (pintype "input"))
    )
    (net (code "92") (name "MUX3_S2") (class "Default")
      (node (ref "TEENSY++") (pin "C3") (pinfunction "13_C3") (pintype "bidirectional"))
      (node (ref "Y") (pin "14") (pinfunction "S2_14") (pintype "input"))
    )
    (net (code "93") (name "MUX3_S3") (class "Default")
      (node (ref "TEENSY++") (pin "C2") (pinfunction "12_C2") (pintype "bidirectional"))
      (node (ref "Y") (pin "13") (pinfunction "S3_13") (pintype "input"))
    )
    (net (code "94") (name "MUX3_SIG") (class "Default")
      (node (ref "TEENSY++") (pin "F3") (pinfunction "41,A3_F3") (pintype "bidirectional"))
      (node (ref "Y") (pin "1") (pinfunction "COM_1") (pintype "bidirectional"))
    )
    (net (code "95") (name "MUX4_S0") (class "Default")
      (node (ref "BUTTONS") (pin "10") (pinfunction "S0_10") (pintype "input"))
      (node (ref "TEENSY++") (pin "B3") (pinfunction "23_B3") (pintype "bidirectional"))
    )
    (net (code "96") (name "MUX4_S1") (class "Default")
      (node (ref "BUTTONS") (pin "11") (pinfunction "S1_11") (pintype "input"))
      (node (ref "TEENSY++") (pin "B2") (pinfunction "22_B2") (pintype "bidirectional"))
    )
    (net (code "97") (name "MUX4_S2") (class "Default")
      (node (ref "BUTTONS") (pin "14") (pinfunction "S2_14") (pintype "input"))
      (node (ref "TEENSY++") (pin "B1") (pinfunction "21_B1") (pintype "bidirectional"))
    )
    (net (code "98") (name "MUX4_S3") (class "Default")
      (node (ref "BUTTONS") (pin "13") (pinfunction "S3_13") (pintype "input"))
      (node (ref "TEENSY++") (pin "B0") (pinfunction "20_B0") (pintype "bidirectional"))
    )
    (net (code "99") (name "MUX4_SIG") (class "Default")
      (node (ref "BUTTONS") (pin "1") (pinfunction "COM_1") (pintype "bidirectional"))
      (node (ref "TEENSY++") (pin "F4") (pinfunction "42,A4_F4") (pintype "bidirectional"))
    )
    (net (code "100") (name "Net-(LED1-PadC)") (class "Default")
      (node (ref "LED1") (pin "C") (pinfunction "C_C") (pintype "passive"))
      (node (ref "R12") (pin "1") (pinfunction "1_1") (pintype "passive"))
    )
    (net (code "101") (name "Net-(Q1-D)") (class "Default")
      (node (ref "J1") (pin "1") (pinfunction "1_1") (pintype "passive"))
      (node (ref "Q1") (pin "3") (pinfunction "D_3") (pintype "passive"))
    )
    (net (code "102") (name "POT_C0") (class "Default")
      (node (ref "POTS") (pin "9") (pinfunction "CHAN0_9") (pintype "bidirectional"))
      (node (ref "POT_1") (pin "1") (pinfunction "1_1") (pintype "passive"))
    )
    (net (code "103") (name "POT_C1") (class "Default")
      (node (ref "POTS") (pin "8") (pinfunction "CHAN1_8") (pintype "bidirectional"))
      (node (ref "POT_1") (pin "2") (pinfunction "2_2") (pintype "passive"))
    )
    (net (code "104") (name "POT_C2") (class "Default")
      (node (ref "POTS") (pin "7") (pinfunction "CHAN2_7") (pintype "bidirectional"))
      (node (ref "POT_1") (pin "3") (pinfunction "3_3") (pintype "passive"))
    )
    (net (code "105") (name "POT_C3") (class "Default")
      (node (ref "POTS") (pin "6") (pinfunction "CHAN3_6") (pintype "bidirectional"))
      (node (ref "POT_1") (pin "4") (pinfunction "4_4") (pintype "passive"))
    )
    (net (code "106") (name "POT_C4") (class "Default")
      (node (ref "POTS") (pin "5") (pinfunction "CHAN4_5") (pintype "bidirectional"))
      (node (ref "POT_2") (pin "1") (pinfunction "1_1") (pintype "passive"))
    )
    (net (code "107") (name "POT_C5") (class "Default")
      (node (ref "POTS") (pin "4") (pinfunction "CHAN5_4") (pintype "bidirectional"))
      (node (ref "POT_2") (pin "2") (pinfunction "2_2") (pintype "passive"))
    )
    (net (code "108") (name "POT_C6") (class "Default")
      (node (ref "POTS") (pin "3") (pinfunction "CHAN6_3") (pintype "bidirectional"))
      (node (ref "POT_2") (pin "3") (pinfunction "3_3") (pintype "passive"))
    )
    (net (code "109") (name "POT_C7") (class "Default")
      (node (ref "POTS") (pin "2") (pinfunction "CHAN7_2") (pintype "bidirectional"))
      (node (ref "POT_2") (pin "4") (pinfunction "4_4") (pintype "passive"))
    )
    (net (code "110") (name "POT_C8") (class "Default")
      (node (ref "POTS") (pin "23") (pinfunction "CHAN8_23") (pintype "bidirectional"))
      (node (ref "POT_3") (pin "1") (pinfunction "1_1") (pintype "passive"))
    )
    (net (code "111") (name "POT_C9") (class "Default")
      (node (ref "POTS") (pin "22") (pinfunction "CHAN9_22") (pintype "bidirectional"))
      (node (ref "POT_3") (pin "2") (pinfunction "2_2") (pintype "passive"))
    )
    (net (code "112") (name "POT_C10") (class "Default")
      (node (ref "POTS") (pin "21") (pinfunction "CHAN10_21") (pintype "bidirectional"))
      (node (ref "POT_3") (pin "3") (pinfunction "3_3") (pintype "passive"))
    )
    (net (code "113") (name "POT_C11") (class "Default")
      (node (ref "POTS") (pin "20") (pinfunction "CHAN11_20") (pintype "bidirectional"))
      (node (ref "POT_3") (pin "4") (pinfunction "4_4") (pintype "passive"))
    )
    (net (code "114") (name "POT_C12") (class "Default")
      (node (ref "POTS") (pin "19") (pinfunction "CHAN12_19") (pintype "bidirectional"))
      (node (ref "POT_4") (pin "1") (pinfunction "1_1") (pintype "passive"))
    )
    (net (code "115") (name "POT_C13") (class "Default")
      (node (ref "POTS") (pin "18") (pinfunction "CHAN13_18") (pintype "bidirectional"))
      (node (ref "POT_4") (pin "2") (pinfunction "2_2") (pintype "passive"))
    )
    (net (code "116") (name "POT_C14") (class "Default")
      (node (ref "POTS") (pin "17") (pinfunction "CHAN14_17") (pintype "bidirectional"))
      (node (ref "POT_4") (pin "3") (pinfunction "3_3") (pintype "passive"))
    )
    (net (code "117") (name "POT_C15") (class "Default")
      (node (ref "POTS") (pin "16") (pinfunction "CHAN15_16") (pintype "bidirectional"))
      (node (ref "POT_4") (pin "4") (pinfunction "4_4") (pintype "passive"))
    )
    (net (code "118") (name "SCL") (class "Default")
      (node (ref "BLUE_DRIVER") (pin "26") (pinfunction "SCL_26") (pintype "bidirectional"))
      (node (ref "I2C") (pin "2") (pinfunction "2_2") (pintype "passive"))
      (node (ref "R1") (pin "P$1") (pinfunction "1_P$1") (pintype "passive"))
      (node (ref "R11") (pin "1") (pinfunction "1_1") (pintype "passive"))
      (node (ref "TEENSY++") (pin "D0") (pinfunction "0,PWM,INT0_D0") (pintype "bidirectional"))
    )
    (net (code "119") (name "SDA") (class "Default")
      (node (ref "BLUE_DRIVER") (pin "27") (pinfunction "SDA_27") (pintype "bidirectional"))
      (node (ref "I2C") (pin "1") (pinfunction "1_1") (pintype "passive"))
      (node (ref "R10") (pin "1") (pinfunction "1_1") (pintype "passive"))
      (node (ref "R2") (pin "P$2") (pinfunction "2_P$2") (pintype "passive"))
      (node (ref "TEENSY++") (pin "D1") (pinfunction "1,PWM,INT1_D1") (pintype "bidirectional"))
    )
    (net (code "120") (name "X_C0") (class "Default")
      (node (ref "X") (pin "9") (pinfunction "CHAN0_9") (pintype "bidirectional"))
      (node (ref "X_1") (pin "1") (pinfunction "1_1") (pintype "passive"))
    )
    (net (code "121") (name "X_C1") (class "Default")
      (node (ref "X") (pin "8") (pinfunction "CHAN1_8") (pintype "bidirectional"))
      (node (ref "X_1") (pin "2") (pinfunction "2_2") (pintype "passive"))
    )
    (net (code "122") (name "X_C2") (class "Default")
      (node (ref "X") (pin "7") (pinfunction "CHAN2_7") (pintype "bidirectional"))
      (node (ref "X_1") (pin "3") (pinfunction "3_3") (pintype "passive"))
    )
    (net (code "123") (name "X_C3") (class "Default")
      (node (ref "X") (pin "6") (pinfunction "CHAN3_6") (pintype "bidirectional"))
      (node (ref "X_1") (pin "4") (pinfunction "4_4") (pintype "passive"))
    )
    (net (code "124") (name "X_C4") (class "Default")
      (node (ref "X") (pin "5") (pinfunction "CHAN4_5") (pintype "bidirectional"))
      (node (ref "X_2") (pin "1") (pinfunction "1_1") (pintype "passive"))
    )
    (net (code "125") (name "X_C5") (class "Default")
      (node (ref "X") (pin "4") (pinfunction "CHAN5_4") (pintype "bidirectional"))
      (node (ref "X_2") (pin "2") (pinfunction "2_2") (pintype "passive"))
    )
    (net (code "126") (name "X_C6") (class "Default")
      (node (ref "X") (pin "3") (pinfunction "CHAN6_3") (pintype "bidirectional"))
      (node (ref "X_2") (pin "3") (pinfunction "3_3") (pintype "passive"))
    )
    (net (code "127") (name "X_C7") (class "Default")
      (node (ref "X") (pin "2") (pinfunction "CHAN7_2") (pintype "bidirectional"))
      (node (ref "X_2") (pin "4") (pinfunction "4_4") (pintype "passive"))
    )
    (net (code "128") (name "X_C8") (class "Default")
      (node (ref "X") (pin "23") (pinfunction "CHAN8_23") (pintype "bidirectional"))
      (node (ref "X_3") (pin "1") (pinfunction "1_1") (pintype "passive"))
    )
    (net (code "129") (name "X_C9") (class "Default")
      (node (ref "X") (pin "22") (pinfunction "CHAN9_22") (pintype "bidirectional"))
      (node (ref "X_3") (pin "2") (pinfunction "2_2") (pintype "passive"))
    )
    (net (code "130") (name "X_C10") (class "Default")
      (node (ref "X") (pin "21") (pinfunction "CHAN10_21") (pintype "bidirectional"))
      (node (ref "X_3") (pin "3") (pinfunction "3_3") (pintype "passive"))
    )
    (net (code "131") (name "X_C11") (class "Default")
      (node (ref "X") (pin "20") (pinfunction "CHAN11_20") (pintype "bidirectional"))
      (node (ref "X_3") (pin "4") (pinfunction "4_4") (pintype "passive"))
    )
    (net (code "132") (name "X_C12") (class "Default")
      (node (ref "X") (pin "19") (pinfunction "CHAN12_19") (pintype "bidirectional"))
      (node (ref "X_4") (pin "1") (pinfunction "1_1") (pintype "passive"))
    )
    (net (code "133") (name "X_C13") (class "Default")
      (node (ref "X") (pin "18") (pinfunction "CHAN13_18") (pintype "bidirectional"))
      (node (ref "X_4") (pin "2") (pinfunction "2_2") (pintype "passive"))
    )
    (net (code "134") (name "X_C14") (class "Default")
      (node (ref "X") (pin "17") (pinfunction "CHAN14_17") (pintype "bidirectional"))
      (node (ref "X_4") (pin "3") (pinfunction "3_3") (pintype "passive"))
    )
    (net (code "135") (name "X_C15") (class "Default")
      (node (ref "X") (pin "16") (pinfunction "CHAN15_16") (pintype "bidirectional"))
      (node (ref "X_4") (pin "4") (pinfunction "4_4") (pintype "passive"))
    )
    (net (code "136") (name "Y_C0") (class "Default")
      (node (ref "Y") (pin "9") (pinfunction "CHAN0_9") (pintype "bidirectional"))
      (node (ref "Y_1") (pin "1") (pinfunction "1_1") (pintype "passive"))
    )
    (net (code "137") (name "Y_C1") (class "Default")
      (node (ref "Y") (pin "8") (pinfunction "CHAN1_8") (pintype "bidirectional"))
      (node (ref "Y_1") (pin "2") (pinfunction "2_2") (pintype "passive"))
    )
    (net (code "138") (name "Y_C2") (class "Default")
      (node (ref "Y") (pin "7") (pinfunction "CHAN2_7") (pintype "bidirectional"))
      (node (ref "Y_1") (pin "3") (pinfunction "3_3") (pintype "passive"))
    )
    (net (code "139") (name "Y_C3") (class "Default")
      (node (ref "Y") (pin "6") (pinfunction "CHAN3_6") (pintype "bidirectional"))
      (node (ref "Y_1") (pin "4") (pinfunction "4_4") (pintype "passive"))
    )
    (net (code "140") (name "Y_C4") (class "Default")
      (node (ref "Y") (pin "5") (pinfunction "CHAN4_5") (pintype "bidirectional"))
      (node (ref "Y_2") (pin "1") (pinfunction "1_1") (pintype "passive"))
    )
    (net (code "141") (name "Y_C5") (class "Default")
      (node (ref "Y") (pin "4") (pinfunction "CHAN5_4") (pintype "bidirectional"))
      (node (ref "Y_2") (pin "2") (pinfunction "2_2") (pintype "passive"))
    )
    (net (code "142") (name "Y_C6") (class "Default")
      (node (ref "Y") (pin "3") (pinfunction "CHAN6_3") (pintype "bidirectional"))
      (node (ref "Y_2") (pin "3") (pinfunction "3_3") (pintype "passive"))
    )
    (net (code "143") (name "Y_C7") (class "Default")
      (node (ref "Y") (pin "2") (pinfunction "CHAN7_2") (pintype "bidirectional"))
      (node (ref "Y_2") (pin "4") (pinfunction "4_4") (pintype "passive"))
    )
    (net (code "144") (name "Y_C8") (class "Default")
      (node (ref "Y") (pin "23") (pinfunction "CHAN8_23") (pintype "bidirectional"))
      (node (ref "Y_3") (pin "1") (pinfunction "1_1") (pintype "passive"))
    )
    (net (code "145") (name "Y_C9") (class "Default")
      (node (ref "Y") (pin "22") (pinfunction "CHAN9_22") (pintype "bidirectional"))
      (node (ref "Y_3") (pin "2") (pinfunction "2_2") (pintype "passive"))
    )
    (net (code "146") (name "Y_C10") (class "Default")
      (node (ref "Y") (pin "21") (pinfunction "CHAN10_21") (pintype "bidirectional"))
      (node (ref "Y_3") (pin "3") (pinfunction "3_3") (pintype "passive"))
    )
    (net (code "147") (name "Y_C11") (class "Default")
      (node (ref "Y") (pin "20") (pinfunction "CHAN11_20") (pintype "bidirectional"))
      (node (ref "Y_3") (pin "4") (pinfunction "4_4") (pintype "passive"))
    )
    (net (code "148") (name "Y_C12") (class "Default")
      (node (ref "Y") (pin "19") (pinfunction "CHAN12_19") (pintype "bidirectional"))
      (node (ref "Y_4") (pin "1") (pinfunction "1_1") (pintype "passive"))
    )
    (net (code "149") (name "Y_C13") (class "Default")
      (node (ref "Y") (pin "18") (pinfunction "CHAN13_18") (pintype "bidirectional"))
      (node (ref "Y_4") (pin "2") (pinfunction "2_2") (pintype "passive"))
    )
    (net (code "150") (name "Y_C14") (class "Default")
      (node (ref "Y") (pin "17") (pinfunction "CHAN14_17") (pintype "bidirectional"))
      (node (ref "Y_4") (pin "3") (pinfunction "3_3") (pintype "passive"))
    )
    (net (code "151") (name "Y_C15") (class "Default")
      (node (ref "Y") (pin "16") (pinfunction "CHAN15_16") (pintype "bidirectional"))
      (node (ref "Y_4") (pin "4") (pinfunction "4_4") (pintype "passive"))
    )
    (net (code "152") (name "unconnected-(TEENSY++-16,PWM-PadC6)") (class "Default")
      (node (ref "TEENSY++") (pin "C6") (pinfunction "16,PWM_C6") (pintype "bidirectional"))
    )
    (net (code "153") (name "unconnected-(TEENSY++-18,INT6-PadE6)") (class "Default")
      (node (ref "TEENSY++") (pin "E6") (pinfunction "18,INT6_E6") (pintype "bidirectional"))
    )
    (net (code "154") (name "unconnected-(TEENSY++-19-PadE7)") (class "Default")
      (node (ref "TEENSY++") (pin "E7") (pinfunction "19_E7") (pintype "bidirectional"))
    )
    (net (code "155") (name "unconnected-(TEENSY++-24,PWM-PadB4)") (class "Default")
      (node (ref "TEENSY++") (pin "B4") (pinfunction "24,PWM_B4") (pintype "bidirectional"))
    )
    (net (code "156") (name "unconnected-(TEENSY++-27,PWM-PadB7)") (class "Default")
      (node (ref "TEENSY++") (pin "B7") (pinfunction "27,PWM_B7") (pintype "bidirectional"))
    )
    (net (code "157") (name "unconnected-(TEENSY++-28-PadA0)") (class "Default")
      (node (ref "TEENSY++") (pin "A0") (pinfunction "28_A0") (pintype "bidirectional"))
    )
    (net (code "158") (name "unconnected-(TEENSY++-29-PadA1)") (class "Default")
      (node (ref "TEENSY++") (pin "A1") (pinfunction "29_A1") (pintype "bidirectional"))
    )
    (net (code "159") (name "unconnected-(TEENSY++-30-PadA2)") (class "Default")
      (node (ref "TEENSY++") (pin "A2") (pinfunction "30_A2") (pintype "bidirectional"))
    )
    (net (code "160") (name "unconnected-(TEENSY++-31-PadA3)") (class "Default")
      (node (ref "TEENSY++") (pin "A3") (pinfunction "31_A3") (pintype "bidirectional"))
    )
    (net (code "161") (name "unconnected-(TEENSY++-32-PadA4)") (class "Default")
      (node (ref "TEENSY++") (pin "A4") (pinfunction "32_A4") (pintype "bidirectional"))
    )
    (net (code "162") (name "unconnected-(TEENSY++-33-PadA5)") (class "Default")
      (node (ref "TEENSY++") (pin "A5") (pinfunction "33_A5") (pintype "bidirectional"))
    )
    (net (code "163") (name "unconnected-(TEENSY++-34-PadA6)") (class "Default")
      (node (ref "TEENSY++") (pin "A6") (pinfunction "34_A6") (pintype "bidirectional"))
    )
    (net (code "164") (name "unconnected-(TEENSY++-35-PadA7)") (class "Default")
      (node (ref "TEENSY++") (pin "A7") (pinfunction "35_A7") (pintype "bidirectional"))
    )
    (net (code "165") (name "unconnected-(TEENSY++-36,INT4-PadE4)") (class "Default")
      (node (ref "TEENSY++") (pin "E4") (pinfunction "36,INT4_E4") (pintype "bidirectional"))
    )
    (net (code "166") (name "unconnected-(TEENSY++-37,INT5-PadE5)") (class "Default")
      (node (ref "TEENSY++") (pin "E5") (pinfunction "37,INT5_E5") (pintype "bidirectional"))
    )
    (net (code "167") (name "unconnected-(TEENSY++-38,A0-PadF0)") (class "Default")
      (node (ref "TEENSY++") (pin "F0") (pinfunction "38,A0_F0") (pintype "bidirectional"))
    )
    (net (code "168") (name "unconnected-(TEENSY++-43,A5-PadF5)") (class "Default")
      (node (ref "TEENSY++") (pin "F5") (pinfunction "43,A5_F5") (pintype "bidirectional"))
    )
    (net (code "169") (name "unconnected-(TEENSY++-44,A6-PadF6)") (class "Default")
      (node (ref "TEENSY++") (pin "F6") (pinfunction "44,A6_F6") (pintype "bidirectional"))
    )
    (net (code "170") (name "unconnected-(TEENSY++-45,A7-PadF7)") (class "Default")
      (node (ref "TEENSY++") (pin "F7") (pinfunction "45,A7_F7") (pintype "bidirectional"))
    )
    (net (code "171") (name "unconnected-(TEENSY++-AREF-PadREF)") (class "Default")
      (node (ref "TEENSY++") (pin "REF") (pinfunction "AREF_REF") (pintype "input"))
    )
    (net (code "172") (name "unconnected-(TEENSY++-_RST-PadRST)") (class "Default")
      (node (ref "TEENSY++") (pin "RST") (pinfunction "_RST_RST") (pintype "input"))
    )
  )
)
